# 02-ESP-WROOM-32.net
KiCad netlist of a schematic drawn in Altium Designer
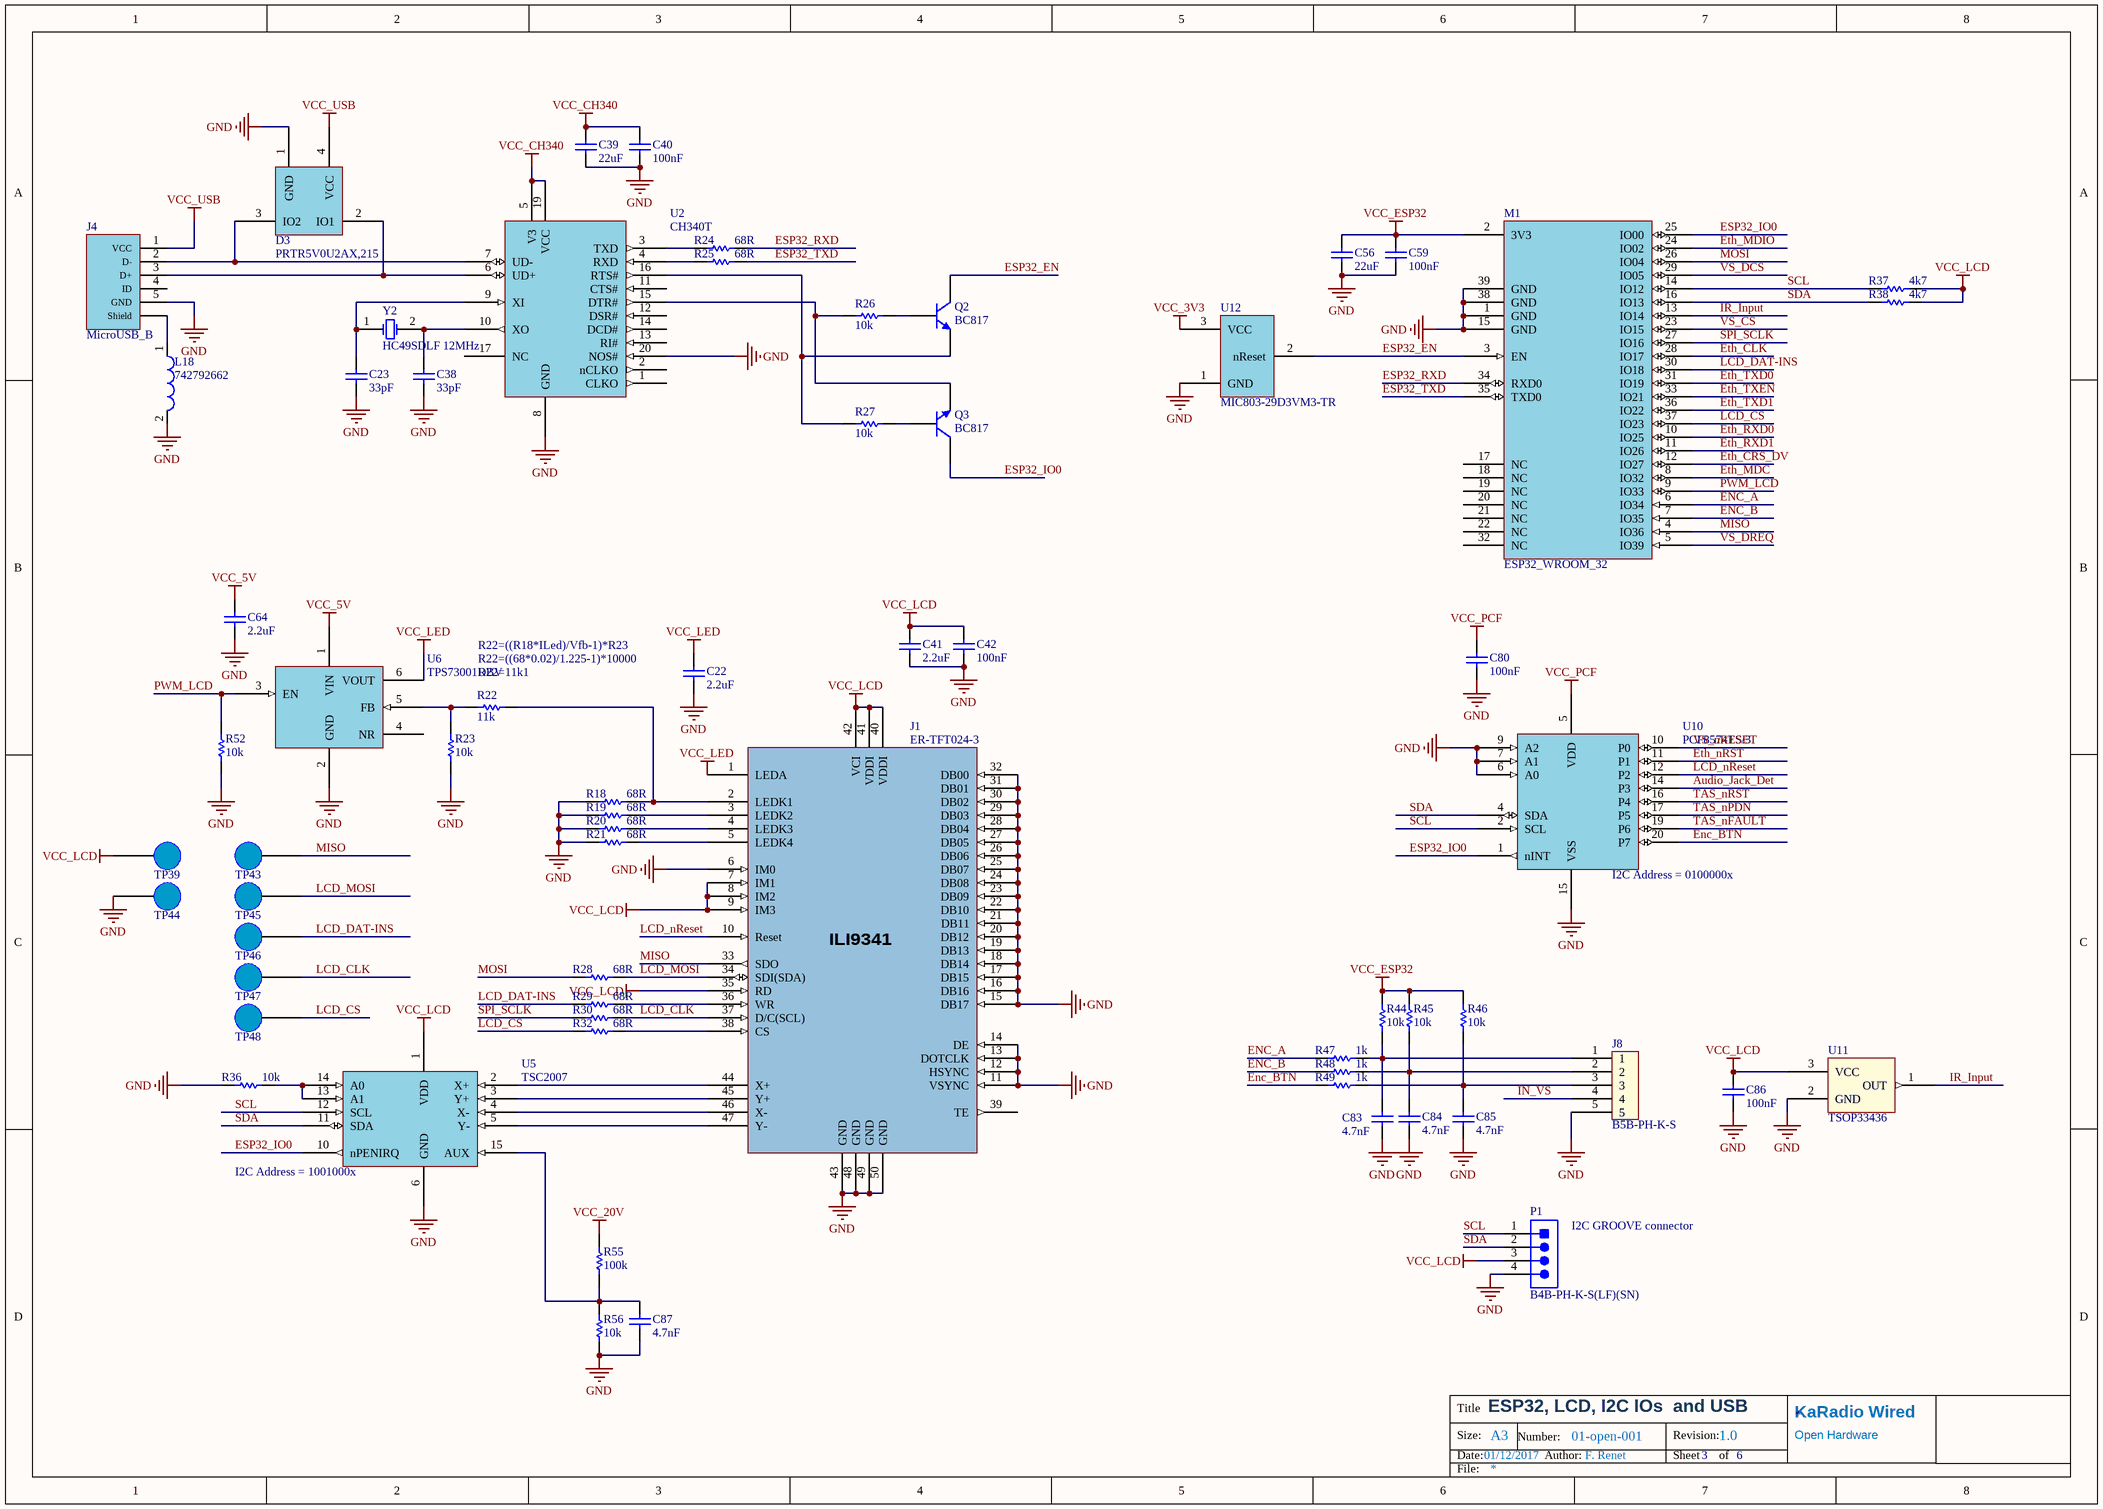
[diagram p0: 02-ESP-WROOM-32.SchDoc]

(export (version "E")
  (design (tool "Eeschema 10.0.6"))
  (components
    (comp (ref "C22")
      (value "2.2uF")
      (footprint "Aptustech:CAPC1608X06N")
      (description "2.2uF 10V 0603 X5R")
      (fields (field (name "VOLTAGE") "10V") (field (name "TOLERANCE") "10%"))
      (libsource (lib "Cap_0603") (part "2.2uF 10V 0603 X5R"))
    )
    (comp (ref "C23")
      (value "33pF")
      (footprint "Aptustech:CAPC1608X06N")
      (description "33pF 50V 0603 NP0")
      (fields (field (name "VOLTAGE") "50V") (field (name "TOLERANCE") "10%"))
      (libsource (lib "Cap_0603") (part "33pF 50V 0603 NP0"))
    )
    (comp (ref "C38")
      (value "33pF")
      (footprint "Aptustech:CAPC1608X06N")
      (description "33pF 50V 0603 NP0")
      (fields (field (name "VOLTAGE") "50V") (field (name "TOLERANCE") "10%"))
      (libsource (lib "Cap_0603") (part "33pF 50V 0603 NP0"))
    )
    (comp (ref "C39")
      (value "22uF")
      (footprint "Aptustech:CAPC1608X06N")
      (description "22uF 6.3V 0603 X5R")
      (fields (field (name "VOLTAGE") "6.3V") (field (name "TOLERANCE") "10%"))
      (libsource (lib "Cap_0603") (part "22uF 6.3V 0603 X5R"))
    )
    (comp (ref "C40")
      (value "100nF")
      (footprint "Aptustech:CAPC1608X06N")
      (description "100nF 25V 0603 X5R")
      (fields (field (name "VOLTAGE") "25V") (field (name "TOLERANCE") "10%"))
      (libsource (lib "Cap_0603") (part "100nF 25V 0603 X5R"))
    )
    (comp (ref "C41")
      (value "2.2uF")
      (footprint "Aptustech:CAPC1608X06N")
      (description "2.2uF 10V 0603 X5R")
      (fields (field (name "VOLTAGE") "10V") (field (name "TOLERANCE") "10%"))
      (libsource (lib "Cap_0603") (part "2.2uF 10V 0603 X5R"))
    )
    (comp (ref "C42")
      (value "100nF")
      (footprint "Aptustech:CAPC1608X06N")
      (description "100nF 25V 0603 X5R")
      (fields (field (name "VOLTAGE") "25V") (field (name "TOLERANCE") "10%"))
      (libsource (lib "Cap_0603") (part "100nF 25V 0603 X5R"))
    )
    (comp (ref "C56")
      (value "22uF")
      (footprint "Aptustech:CAPC1608X06N")
      (description "22uF 6.3V 0603 X5R")
      (fields (field (name "VOLTAGE") "6.3V") (field (name "TOLERANCE") "10%"))
      (libsource (lib "Cap_0603") (part "22uF 6.3V 0603 X5R"))
    )
    (comp (ref "C59")
      (value "100nF")
      (footprint "Aptustech:CAPC1608X06N")
      (description "100nF 25V 0603 X5R")
      (fields (field (name "VOLTAGE") "25V") (field (name "TOLERANCE") "10%"))
      (libsource (lib "Cap_0603") (part "100nF 25V 0603 X5R"))
    )
    (comp (ref "C64")
      (value "2.2uF")
      (footprint "Aptustech:CAPC1608X06N")
      (description "2.2uF 10V 0603 X5R")
      (fields (field (name "VOLTAGE") "10V") (field (name "TOLERANCE") "10%"))
      (libsource (lib "Cap_0603") (part "2.2uF 10V 0603 X5R"))
    )
    (comp (ref "C80")
      (value "100nF")
      (footprint "Aptustech:CAPC1608X06N")
      (description "100nF 25V 0603 X5R")
      (fields (field (name "VOLTAGE") "25V") (field (name "TOLERANCE") "10%"))
      (libsource (lib "Cap_0603") (part "100nF 25V 0603 X5R"))
    )
    (comp (ref "C83")
      (value "4.7nF")
      (footprint "CAPC1608X06N")
      (description "4.7nF 50V 0603 X7R")
      (fields (field (name "VOLTAGE") "50V") (field (name "TOLERANCE") "10%"))
      (libsource (lib "Cap_0603") (part "4.7nF 50V 0603 X7R"))
    )
    (comp (ref "C84")
      (value "4.7nF")
      (footprint "CAPC1608X06N")
      (description "4.7nF 50V 0603 X7R")
      (fields (field (name "VOLTAGE") "50V") (field (name "TOLERANCE") "10%"))
      (libsource (lib "Cap_0603") (part "4.7nF 50V 0603 X7R"))
    )
    (comp (ref "C85")
      (value "4.7nF")
      (footprint "CAPC1608X06N")
      (description "4.7nF 50V 0603 X7R")
      (fields (field (name "VOLTAGE") "50V") (field (name "TOLERANCE") "10%"))
      (libsource (lib "Cap_0603") (part "4.7nF 50V 0603 X7R"))
    )
    (comp (ref "C86")
      (value "100nF")
      (footprint "CAPC1608X06N")
      (description "100nF 25V 0603 X5R")
      (fields (field (name "VOLTAGE") "25V") (field (name "TOLERANCE") "10%"))
      (libsource (lib "Cap_0603") (part "100nF 25V 0603 X5R"))
    )
    (comp (ref "C87")
      (value "4.7nF")
      (footprint "Aptustech:CAPC1608X06N")
      (description "4.7nF 50V 0603 X7R")
      (fields (field (name "VOLTAGE") "50V") (field (name "TOLERANCE") "10%"))
      (libsource (lib "Cap_0603") (part "4.7nF 50V 0603 X7R"))
    )
    (comp (ref "D3")
      (value "PRTR5V0U2AX,215")
      (footprint "Aptustech:SOT190P230X120-4N")
      (description "Ultra low capacitance double rail-to-rail ESD protection diode")
      (fields (field (name "MANUFACTURER") "Nexperia"))
      (libsource (lib "Diodes") (part "PRTR5V0U2AX,215"))
    )
    (comp (ref "J1")
      (value "ER-TFT024-3")
      (footprint "Aptustech:62684-501100ALF")
      (description "Connector for 240x320 dots 2.4\" color tft lcd module")
      (fields (field (name "PARTNUMBER") "62684-501100ALF") (field (name "MANUFACTURER") "Amphenol FCI"))
      (libsource (lib "AptusTech") (part "ER-TFT024-3"))
    )
    (comp (ref "J4")
      (value "MicroUSB_B")
      (footprint "Aptustech:629105150521")
      (description "Micro USB 2.0 SMT Type B Horizontal")
      (fields (field (name "PARTNUMBER") "629105150521") (field (name "MANUFACTURER") "Wurth Elektronik"))
      (libsource (lib "Connectors") (part "MicroUSB_B"))
    )
    (comp (ref "J8")
      (value "B5B-PH-K-S")
      (footprint "PcbLib:JST-B5B-PH-K-S_V")
      (description "JST  B5B-PH 2mm Pitch 5pins TH")
      (fields (field (name "MANUFACTURER") "JST") (field (name "PARTNUMBER") "B5B-PH-K-S"))
      (libsource (lib "Connectors") (part "B5B-PH-K-S"))
    )
    (comp (ref "L18")
      (value "742792662")
      (footprint "CAPC0603(1608)")
      (description "SMD EMI Suppression Ferrite Bead WE-CBF, Z = 1000 Ohm")
      (fields (field (name "MANUFACTURER") "Wurth"))
      (libsource (lib "altium-import") (part "root_3_CMP-0220-00178-1_"))
    )
    (comp (ref "M1")
      (value "ESP32_WROOM_32")
      (footprint "Aptustech:ESP-WROOM-32")
      (fields (field (name "MANUFACTURER") "Espressif Systems"))
      (libsource (lib "Modules") (part "ESP32_WROOM_32"))
    )
    (comp (ref "P1")
      (value "B4B-PH-K-S(LF)(SN)")
      (footprint "Aptustech:JST-B4B-PH-K-S_V")
      (description "Male Header, Pitch 2 mm, 1 x 4 Position")
      (fields (field (name "MANUFACTURER") "JST"))
      (libsource (lib "altium-import") (part "root_0_CN-1P-M-R4_"))
    )
    (comp (ref "Q2")
      (value "BC817")
      (footprint "Aptustech:SOT95P230X110-3N")
      (description "BC817 NPN  45V SOT23")
      (fields (field (name "PARTNUMBER") "BC817-40,215") (field (name "MANUFACTURER") "Nexperia"))
      (libsource (lib "Transistor_Switch") (part "BC817_SOT23"))
    )
    (comp (ref "Q3")
      (value "BC817")
      (footprint "Aptustech:SOT95P230X110-3N")
      (description "BC817 NPN  45V SOT23")
      (fields (field (name "PARTNUMBER") "BC817-40,215") (field (name "MANUFACTURER") "Nexperia"))
      (libsource (lib "Transistor_Switch") (part "BC817_SOT23"))
    )
    (comp (ref "R18")
      (value "68R")
      (footprint "Aptustech:RESC1608X06N")
      (description "Resistor 68R 0603 1%")
      (fields (field (name "TOLERANCE") "1%") (field (name "Comment") "68R_0603"))
      (libsource (lib "Res_0603") (part "68R"))
    )
    (comp (ref "R19")
      (value "68R")
      (footprint "Aptustech:RESC1608X06N")
      (description "Resistor 68R 0603 1%")
      (fields (field (name "TOLERANCE") "1%") (field (name "Comment") "68R_0603"))
      (libsource (lib "Res_0603") (part "68R"))
    )
    (comp (ref "R20")
      (value "68R")
      (footprint "Aptustech:RESC1608X06N")
      (description "Resistor 68R 0603 1%")
      (fields (field (name "TOLERANCE") "1%") (field (name "Comment") "68R_0603"))
      (libsource (lib "Res_0603") (part "68R"))
    )
    (comp (ref "R21")
      (value "68R")
      (footprint "Aptustech:RESC1608X06N")
      (description "Resistor 68R 0603 1%")
      (fields (field (name "TOLERANCE") "1%") (field (name "Comment") "68R_0603"))
      (libsource (lib "Res_0603") (part "68R"))
    )
    (comp (ref "R22")
      (value "11k")
      (footprint "Aptustech:RESC1608X06N")
      (description "Resistor 11k 0603 1%")
      (fields (field (name "TOLERANCE") "1%") (field (name "Comment") "11k_0603"))
      (libsource (lib "Res_0603") (part "11k"))
    )
    (comp (ref "R23")
      (value "10k")
      (footprint "Aptustech:RESC1608X06N")
      (description "Resistor 10k 0603 1%")
      (fields (field (name "TOLERANCE") "1%") (field (name "Comment") "10k_0603"))
      (libsource (lib "Res_0603") (part "10k"))
    )
    (comp (ref "R24")
      (value "68R")
      (footprint "Aptustech:RESC1608X06N")
      (description "Resistor 68R 0603 1%")
      (fields (field (name "TOLERANCE") "1%") (field (name "Comment") "68R_0603"))
      (libsource (lib "Res_0603") (part "68R"))
    )
    (comp (ref "R25")
      (value "68R")
      (footprint "Aptustech:RESC1608X06N")
      (description "Resistor 68R 0603 1%")
      (fields (field (name "TOLERANCE") "1%") (field (name "Comment") "68R_0603"))
      (libsource (lib "Res_0603") (part "68R"))
    )
    (comp (ref "R26")
      (value "10k")
      (footprint "Aptustech:RESC1608X06N")
      (description "Resistor 10k 0603 1%")
      (fields (field (name "TOLERANCE") "1%") (field (name "Comment") "10k_0603"))
      (libsource (lib "Res_0603") (part "10k"))
    )
    (comp (ref "R27")
      (value "10k")
      (footprint "Aptustech:RESC1608X06N")
      (description "Resistor 10k 0603 1%")
      (fields (field (name "TOLERANCE") "1%") (field (name "Comment") "10k_0603"))
      (libsource (lib "Res_0603") (part "10k"))
    )
    (comp (ref "R28")
      (value "68R")
      (footprint "Aptustech:RESC1608X06N")
      (description "Resistor 68R 0603 1%")
      (fields (field (name "TOLERANCE") "1%") (field (name "Comment") "68R_0603"))
      (libsource (lib "Res_0603") (part "68R"))
    )
    (comp (ref "R29")
      (value "68R")
      (footprint "Aptustech:RESC1608X06N")
      (description "Resistor 68R 0603 1%")
      (fields (field (name "TOLERANCE") "1%") (field (name "Comment") "68R_0603"))
      (libsource (lib "Res_0603") (part "68R"))
    )
    (comp (ref "R30")
      (value "68R")
      (footprint "Aptustech:RESC1608X06N")
      (description "Resistor 68R 0603 1%")
      (fields (field (name "TOLERANCE") "1%") (field (name "Comment") "68R_0603"))
      (libsource (lib "Res_0603") (part "68R"))
    )
    (comp (ref "R32")
      (value "68R")
      (footprint "Aptustech:RESC1608X06N")
      (description "Resistor 68R 0603 1%")
      (fields (field (name "TOLERANCE") "1%") (field (name "Comment") "68R_0603"))
      (libsource (lib "Res_0603") (part "68R"))
    )
    (comp (ref "R36")
      (value "10k")
      (footprint "Aptustech:RESC1608X06N")
      (description "Resistor 10k 0603 1%")
      (fields (field (name "TOLERANCE") "1%") (field (name "Comment") "10k_0603"))
      (libsource (lib "Res_0603") (part "10k"))
    )
    (comp (ref "R37")
      (value "4k7")
      (footprint "Aptustech:RESC1608X06N")
      (description "Resistor 4k7 0603 1%")
      (fields (field (name "TOLERANCE") "1%") (field (name "Comment") "4k7_0603"))
      (libsource (lib "Res_0603") (part "4k7"))
    )
    (comp (ref "R38")
      (value "4k7")
      (footprint "Aptustech:RESC1608X06N")
      (description "Resistor 4k7 0603 1%")
      (fields (field (name "TOLERANCE") "1%") (field (name "Comment") "4k7_0603"))
      (libsource (lib "Res_0603") (part "4k7"))
    )
    (comp (ref "R44")
      (value "10k")
      (footprint "RESC1608X06N")
      (description "Resistor 10k 0603 1%")
      (fields (field (name "TOLERANCE") "1%") (field (name "Comment") "10k_0603"))
      (libsource (lib "Res_0603") (part "10k"))
    )
    (comp (ref "R45")
      (value "10k")
      (footprint "RESC1608X06N")
      (description "Resistor 10k 0603 1%")
      (fields (field (name "TOLERANCE") "1%") (field (name "Comment") "10k_0603"))
      (libsource (lib "Res_0603") (part "10k"))
    )
    (comp (ref "R46")
      (value "10k")
      (footprint "RESC1608X06N")
      (description "Resistor 10k 0603 1%")
      (fields (field (name "TOLERANCE") "1%") (field (name "Comment") "10k_0603"))
      (libsource (lib "Res_0603") (part "10k"))
    )
    (comp (ref "R47")
      (value "1k")
      (footprint "RESC1608X06N")
      (description "Resistor 1k 0603 1%")
      (fields (field (name "TOLERANCE") "1%") (field (name "Comment") "1k_0603"))
      (libsource (lib "Res_0603") (part "1k"))
    )
    (comp (ref "R48")
      (value "1k")
      (footprint "RESC1608X06N")
      (description "Resistor 1k 0603 1%")
      (fields (field (name "TOLERANCE") "1%") (field (name "Comment") "1k_0603"))
      (libsource (lib "Res_0603") (part "1k"))
    )
    (comp (ref "R49")
      (value "1k")
      (footprint "RESC1608X06N")
      (description "Resistor 1k 0603 1%")
      (fields (field (name "TOLERANCE") "1%") (field (name "Comment") "1k_0603"))
      (libsource (lib "Res_0603") (part "1k"))
    )
    (comp (ref "R52")
      (value "10k")
      (footprint "Aptustech:RESC1608X06N")
      (description "Resistor 10k 0603 1%")
      (fields (field (name "TOLERANCE") "1%") (field (name "Comment") "10k_0603"))
      (libsource (lib "Res_0603") (part "10k"))
    )
    (comp (ref "R55")
      (value "100k")
      (footprint "Aptustech:RESC1608X06N")
      (description "Resistor 100k 0603 1%")
      (fields (field (name "TOLERANCE") "1%") (field (name "Comment") "100k_0603"))
      (libsource (lib "Res_0603") (part "100k"))
    )
    (comp (ref "R56")
      (value "10k")
      (footprint "Aptustech:RESC1608X06N")
      (description "Resistor 10k 0603 1%")
      (fields (field (name "TOLERANCE") "1%") (field (name "Comment") "10k_0603"))
      (libsource (lib "Res_0603") (part "10k"))
    )
    (comp (ref "TP39")
      (value "TP_1mm")
      (footprint "Aptustech:TP_1mm")
      (description "Test point 1mm round SMD")
      (libsource (lib "Mech") (part "TP_1mm"))
    )
    (comp (ref "TP43")
      (value "TP_1mm")
      (footprint "Aptustech:TP_1mm")
      (description "Test point 1mm round SMD")
      (libsource (lib "Mech") (part "TP_1mm"))
    )
    (comp (ref "TP44")
      (value "TP_1mm")
      (footprint "Aptustech:TP_1mm")
      (description "Test point 1mm round SMD")
      (libsource (lib "Mech") (part "TP_1mm"))
    )
    (comp (ref "TP45")
      (value "TP_1mm")
      (footprint "Aptustech:TP_1mm")
      (description "Test point 1mm round SMD")
      (libsource (lib "Mech") (part "TP_1mm"))
    )
    (comp (ref "TP46")
      (value "TP_1mm")
      (footprint "Aptustech:TP_1mm")
      (description "Test point 1mm round SMD")
      (libsource (lib "Mech") (part "TP_1mm"))
    )
    (comp (ref "TP47")
      (value "TP_1mm")
      (footprint "Aptustech:TP_1mm")
      (description "Test point 1mm round SMD")
      (libsource (lib "Mech") (part "TP_1mm"))
    )
    (comp (ref "TP48")
      (value "TP_1mm")
      (footprint "Aptustech:TP_1mm")
      (description "Test point 1mm round SMD")
      (libsource (lib "Mech") (part "TP_1mm"))
    )
    (comp (ref "U2")
      (value "CH340T")
      (footprint "Aptustech:TSOP65P780X120-20N")
      (description "CH340T USB to Serial")
      (fields (field (name "MANUFACTURER") "WCH"))
      (libsource (lib "MISC_IC") (part "CH340T"))
    )
    (comp (ref "U5")
      (value "TSC2007")
      (footprint "Aptustech:TSOP65P640X120-16N")
      (description "TSSOP I2C Resistive Touch Controller")
      (fields (field (name "PARTNUMBER") "TSC2007IPWR") (field (name "MANUFACTURER") "TI"))
      (libsource (lib "MISC_IC") (part "TSC2007"))
    )
    (comp (ref "U6")
      (value "TPS73001DBV")
      (footprint "Aptustech:SOT95P245X110-6N")
      (description "TPS730 ADJ 200mA SOT23-6 LDO")
      (fields (field (name "MANUFACTURER") "TI"))
      (libsource (lib "LDO_DC-DC") (part "TPS73001DBV"))
    )
    (comp (ref "U10")
      (value "PCF8574TS/3")
      (footprint "Aptustech:TSOP65P640X120-20N")
      (description "PCF8574TS/3 SSOP20 I2C I/O Expander")
      (fields (field (name "MANUFACTURER") "NXP"))
      (libsource (lib "MISC_IC") (part "PCF8574TS/3"))
    )
    (comp (ref "U11")
      (value "TSOP33436")
      (footprint "PcbLib:TSOP332")
      (description "TSOP33436 IR 36kHz Receiver")
      (fields (field (name "MANUFACTURER") "Vishay"))
      (libsource (lib "KaRAD_EXT") (part "TSOP33436"))
    )
    (comp (ref "U12")
      (value "MIC803-29D3VM3-TR")
      (footprint "Aptustech:SOT95P230X110-3N")
      (description "Reset 2.93V open drain sot23 MIC803-29D3VM3-TR")
      (fields (field (name "MANUFACTURER") "Microchip"))
      (libsource (lib "MISC_IC") (part "MIC803-29D3VM3-TR"))
    )
    (comp (ref "Y2")
      (value "HC49SDLF 12MHz")
      (footprint "Aptustech:TXC 9C")
      (description "12.0000MHz Crystal HC49 SMT 20ppm")
      (fields (field (name "PARTNUMBER") "GC1200052") (field (name "MANUFACTURER") "Diodes"))
      (libsource (lib "Crystal_OSC") (part "HC49SDLF 12.000MHz"))
    )
  )
  (nets
    (net (code "1") (name "/Audio_Jack_Det") (class "Default")
      (node (ref "U10") (pin "14") (pinfunction "P3_14") (pintype "bidirectional"))
    )
    (net (code "2") (name "/ENC_A") (class "Default")
      (node (ref "M1") (pin "6") (pinfunction "IO34_6") (pintype "input"))
      (node (ref "R47") (pin "1") (pinfunction "1_1") (pintype "passive"))
    )
    (net (code "3") (name "/ENC_B") (class "Default")
      (node (ref "M1") (pin "7") (pinfunction "IO35_7") (pintype "input"))
      (node (ref "R48") (pin "1") (pinfunction "1_1") (pintype "passive"))
    )
    (net (code "4") (name "/ESP32_EN") (class "Default")
      (node (ref "M1") (pin "3") (pinfunction "EN_3") (pintype "input"))
      (node (ref "Q2") (pin "3") (pinfunction "C_3") (pintype "passive"))
      (node (ref "U12") (pin "2") (pinfunction "nReset_2") (pintype "open_collector"))
    )
    (net (code "5") (name "/ESP32_IO0") (class "Default")
      (node (ref "M1") (pin "25") (pinfunction "IO00_25") (pintype "bidirectional"))
      (node (ref "Q3") (pin "3") (pinfunction "C_3") (pintype "passive"))
      (node (ref "U10") (pin "1") (pinfunction "nINT_1") (pintype "output"))
      (node (ref "U5") (pin "10") (pinfunction "nPENIRQ_10") (pintype "output"))
    )
    (net (code "6") (name "/ESP32_RXD") (class "Default")
      (node (ref "M1") (pin "34") (pinfunction "RXD0_34") (pintype "bidirectional"))
      (node (ref "R24") (pin "2") (pinfunction "2_2") (pintype "passive"))
    )
    (net (code "7") (name "/ESP32_TXD") (class "Default")
      (node (ref "M1") (pin "35") (pinfunction "TXD0_35") (pintype "bidirectional"))
      (node (ref "R25") (pin "2") (pinfunction "2_2") (pintype "passive"))
    )
    (net (code "8") (name "/Enc_BTN") (class "Default")
      (node (ref "R49") (pin "1") (pinfunction "1_1") (pintype "passive"))
      (node (ref "U10") (pin "20") (pinfunction "P7_20") (pintype "bidirectional"))
    )
    (net (code "9") (name "/Eth_CLK") (class "Default")
      (node (ref "M1") (pin "28") (pinfunction "IO17_28") (pintype "bidirectional"))
    )
    (net (code "10") (name "/Eth_CRS_DV") (class "Default")
      (node (ref "M1") (pin "12") (pinfunction "IO27_12") (pintype "bidirectional"))
    )
    (net (code "11") (name "/Eth_MDC") (class "Default")
      (node (ref "M1") (pin "8") (pinfunction "IO32_8") (pintype "bidirectional"))
    )
    (net (code "12") (name "/Eth_MDIO") (class "Default")
      (node (ref "M1") (pin "24") (pinfunction "IO02_24") (pintype "bidirectional"))
    )
    (net (code "13") (name "/Eth_RXD0") (class "Default")
      (node (ref "M1") (pin "10") (pinfunction "IO25_10") (pintype "bidirectional"))
    )
    (net (code "14") (name "/Eth_RXD1") (class "Default")
      (node (ref "M1") (pin "11") (pinfunction "IO26_11") (pintype "bidirectional"))
    )
    (net (code "15") (name "/Eth_TXD0") (class "Default")
      (node (ref "M1") (pin "31") (pinfunction "IO19_31") (pintype "bidirectional"))
    )
    (net (code "16") (name "/Eth_TXD1") (class "Default")
      (node (ref "M1") (pin "36") (pinfunction "IO22_36") (pintype "bidirectional"))
    )
    (net (code "17") (name "/Eth_TXEN") (class "Default")
      (node (ref "M1") (pin "33") (pinfunction "IO21_33") (pintype "bidirectional"))
    )
    (net (code "18") (name "/Eth_nRST") (class "Default")
      (node (ref "U10") (pin "11") (pinfunction "P1_11") (pintype "bidirectional"))
    )
    (net (code "19") (name "/IN_VS") (class "Default")
      (node (ref "J8") (pin "4") (pinfunction "4_4") (pintype "power_in"))
    )
    (net (code "20") (name "/IR_Input") (class "Default")
      (node (ref "M1") (pin "13") (pinfunction "IO14_13") (pintype "bidirectional"))
      (node (ref "U11") (pin "1") (pinfunction "OUT_1") (pintype "output"))
    )
    (net (code "21") (name "/LCD_CLK") (class "Default")
      (node (ref "J1") (pin "37") (pinfunction "D/C(SCL)_37") (pintype "input"))
      (node (ref "R30") (pin "2") (pinfunction "2_2") (pintype "passive"))
      (node (ref "TP47") (pin "1") (pinfunction "1_1") (pintype "passive"))
    )
    (net (code "22") (name "/LCD_CS") (class "Default")
      (node (ref "M1") (pin "37") (pinfunction "IO23_37") (pintype "bidirectional"))
      (node (ref "R32") (pin "1") (pinfunction "1_1") (pintype "passive"))
      (node (ref "TP48") (pin "1") (pinfunction "1_1") (pintype "passive"))
    )
    (net (code "23") (name "/LCD_DAT-INS") (class "Default")
      (node (ref "M1") (pin "30") (pinfunction "IO18_30") (pintype "bidirectional"))
      (node (ref "R29") (pin "1") (pinfunction "1_1") (pintype "passive"))
      (node (ref "TP46") (pin "1") (pinfunction "1_1") (pintype "passive"))
    )
    (net (code "24") (name "/LCD_MOSI") (class "Default")
      (node (ref "J1") (pin "34") (pinfunction "SDI(SDA)_34") (pintype "bidirectional"))
      (node (ref "R28") (pin "2") (pinfunction "2_2") (pintype "passive"))
      (node (ref "TP45") (pin "1") (pinfunction "1_1") (pintype "passive"))
    )
    (net (code "25") (name "/LCD_nReset") (class "Default")
      (node (ref "J1") (pin "10") (pinfunction "Reset_10") (pintype "input"))
      (node (ref "U10") (pin "12") (pinfunction "P2_12") (pintype "bidirectional"))
    )
    (net (code "26") (name "/MISO") (class "Default")
      (node (ref "J1") (pin "33") (pinfunction "SDO_33") (pintype "output"))
      (node (ref "M1") (pin "4") (pinfunction "IO36_4") (pintype "input"))
      (node (ref "TP43") (pin "1") (pinfunction "1_1") (pintype "passive"))
    )
    (net (code "27") (name "/MOSI") (class "Default")
      (node (ref "M1") (pin "26") (pinfunction "IO04_26") (pintype "bidirectional"))
      (node (ref "R28") (pin "1") (pinfunction "1_1") (pintype "passive"))
    )
    (net (code "28") (name "/PWM_LCD") (class "Default")
      (node (ref "M1") (pin "9") (pinfunction "IO33_9") (pintype "bidirectional"))
      (node (ref "R52") (pin "2") (pinfunction "2_2") (pintype "passive"))
      (node (ref "U6") (pin "3") (pinfunction "EN_3") (pintype "input"))
    )
    (net (code "29") (name "/SCL") (class "Default")
      (node (ref "M1") (pin "14") (pinfunction "IO12_14") (pintype "bidirectional"))
      (node (ref "P1") (pin "1") (pinfunction "1_1") (pintype "passive"))
      (node (ref "R37") (pin "1") (pinfunction "1_1") (pintype "passive"))
      (node (ref "U10") (pin "2") (pinfunction "SCL_2") (pintype "input"))
      (node (ref "U5") (pin "12") (pinfunction "SCL_12") (pintype "input"))
    )
    (net (code "30") (name "/SDA") (class "Default")
      (node (ref "M1") (pin "16") (pinfunction "IO13_16") (pintype "bidirectional"))
      (node (ref "P1") (pin "2") (pinfunction "2_2") (pintype "passive"))
      (node (ref "R38") (pin "1") (pinfunction "1_1") (pintype "passive"))
      (node (ref "U10") (pin "4") (pinfunction "SDA_4") (pintype "bidirectional"))
      (node (ref "U5") (pin "11") (pinfunction "SDA_11") (pintype "bidirectional"))
    )
    (net (code "31") (name "/SPI_SCLK") (class "Default")
      (node (ref "M1") (pin "27") (pinfunction "IO16_27") (pintype "bidirectional"))
      (node (ref "R30") (pin "1") (pinfunction "1_1") (pintype "passive"))
    )
    (net (code "32") (name "/TAS_nFAULT") (class "Default")
      (node (ref "U10") (pin "19") (pinfunction "P6_19") (pintype "bidirectional"))
    )
    (net (code "33") (name "/TAS_nPDN") (class "Default")
      (node (ref "U10") (pin "17") (pinfunction "P5_17") (pintype "bidirectional"))
    )
    (net (code "34") (name "/TAS_nRST") (class "Default")
      (node (ref "U10") (pin "16") (pinfunction "P4_16") (pintype "bidirectional"))
    )
    (net (code "35") (name "/VS_CS") (class "Default")
      (node (ref "M1") (pin "23") (pinfunction "IO15_23") (pintype "bidirectional"))
    )
    (net (code "36") (name "/VS_DCS") (class "Default")
      (node (ref "M1") (pin "29") (pinfunction "IO05_29") (pintype "bidirectional"))
    )
    (net (code "37") (name "/VS_DREQ") (class "Default")
      (node (ref "M1") (pin "5") (pinfunction "IO39_5") (pintype "input"))
    )
    (net (code "38") (name "/VS_nRESET") (class "Default")
      (node (ref "U10") (pin "10") (pinfunction "P0_10") (pintype "bidirectional"))
    )
    (net (code "39") (name "GND") (class "Default")
      (node (ref "C22") (pin "1") (pinfunction "1_1") (pintype "passive"))
      (node (ref "C23") (pin "1") (pinfunction "1_1") (pintype "passive"))
      (node (ref "C38") (pin "1") (pinfunction "1_1") (pintype "passive"))
      (node (ref "C39") (pin "2") (pinfunction "2_2") (pintype "passive"))
      (node (ref "C40") (pin "2") (pinfunction "2_2") (pintype "passive"))
      (node (ref "C41") (pin "1") (pinfunction "1_1") (pintype "passive"))
      (node (ref "C42") (pin "2") (pinfunction "2_2") (pintype "passive"))
      (node (ref "C56") (pin "2") (pinfunction "2_2") (pintype "passive"))
      (node (ref "C59") (pin "2") (pinfunction "2_2") (pintype "passive"))
      (node (ref "C64") (pin "1") (pinfunction "1_1") (pintype "passive"))
      (node (ref "C80") (pin "2") (pinfunction "2_2") (pintype "passive"))
      (node (ref "C83") (pin "1") (pinfunction "1_1") (pintype "passive"))
      (node (ref "C84") (pin "1") (pinfunction "1_1") (pintype "passive"))
      (node (ref "C85") (pin "1") (pinfunction "1_1") (pintype "passive"))
      (node (ref "C86") (pin "2") (pinfunction "2_2") (pintype "passive"))
      (node (ref "C87") (pin "1") (pinfunction "1_1") (pintype "passive"))
      (node (ref "D3") (pin "1") (pinfunction "GND_1") (pintype "power_in"))
      (node (ref "J1") (pin "11") (pinfunction "VSYNC_11") (pintype "input"))
      (node (ref "J1") (pin "12") (pinfunction "HSYNC_12") (pintype "input"))
      (node (ref "J1") (pin "13") (pinfunction "DOTCLK_13") (pintype "input"))
      (node (ref "J1") (pin "14") (pinfunction "DE_14") (pintype "input"))
      (node (ref "J1") (pin "15") (pinfunction "DB17_15") (pintype "input"))
      (node (ref "J1") (pin "16") (pinfunction "DB16_16") (pintype "input"))
      (node (ref "J1") (pin "17") (pinfunction "DB15_17") (pintype "input"))
      (node (ref "J1") (pin "18") (pinfunction "DB14_18") (pintype "input"))
      (node (ref "J1") (pin "19") (pinfunction "DB13_19") (pintype "input"))
      (node (ref "J1") (pin "20") (pinfunction "DB12_20") (pintype "input"))
      (node (ref "J1") (pin "21") (pinfunction "DB11_21") (pintype "input"))
      (node (ref "J1") (pin "22") (pinfunction "DB10_22") (pintype "input"))
      (node (ref "J1") (pin "23") (pinfunction "DB09_23") (pintype "input"))
      (node (ref "J1") (pin "24") (pinfunction "DB08_24") (pintype "input"))
      (node (ref "J1") (pin "25") (pinfunction "DB07_25") (pintype "input"))
      (node (ref "J1") (pin "26") (pinfunction "DB06_26") (pintype "input"))
      (node (ref "J1") (pin "27") (pinfunction "DB05_27") (pintype "input"))
      (node (ref "J1") (pin "28") (pinfunction "DB04_28") (pintype "input"))
      (node (ref "J1") (pin "29") (pinfunction "DB03_29") (pintype "input"))
      (node (ref "J1") (pin "30") (pinfunction "DB02_30") (pintype "input"))
      (node (ref "J1") (pin "31") (pinfunction "DB01_31") (pintype "input"))
      (node (ref "J1") (pin "32") (pinfunction "DB00_32") (pintype "input"))
      (node (ref "J1") (pin "43") (pinfunction "GND_43") (pintype "power_in"))
      (node (ref "J1") (pin "48") (pinfunction "GND_48") (pintype "power_in"))
      (node (ref "J1") (pin "49") (pinfunction "GND_49") (pintype "power_in"))
      (node (ref "J1") (pin "50") (pinfunction "GND_50") (pintype "power_in"))
      (node (ref "J1") (pin "6") (pinfunction "IM0_6") (pintype "input"))
      (node (ref "J4") (pin "5") (pinfunction "GND_5") (pintype "passive"))
      (node (ref "J8") (pin "5") (pinfunction "5_5") (pintype "power_in"))
      (node (ref "L18") (pin "2") (pinfunction "2_2") (pintype "passive"))
      (node (ref "M1") (pin "1") (pinfunction "GND_1") (pintype "power_in"))
      (node (ref "M1") (pin "15") (pinfunction "GND_15") (pintype "power_in"))
      (node (ref "M1") (pin "38") (pinfunction "GND_38") (pintype "power_in"))
      (node (ref "M1") (pin "39") (pinfunction "GND_39") (pintype "power_in"))
      (node (ref "P1") (pin "4") (pinfunction "4_4") (pintype "passive"))
      (node (ref "R18") (pin "1") (pinfunction "1_1") (pintype "passive"))
      (node (ref "R19") (pin "1") (pinfunction "1_1") (pintype "passive"))
      (node (ref "R20") (pin "1") (pinfunction "1_1") (pintype "passive"))
      (node (ref "R21") (pin "1") (pinfunction "1_1") (pintype "passive"))
      (node (ref "R23") (pin "1") (pinfunction "1_1") (pintype "passive"))
      (node (ref "R36") (pin "2") (pinfunction "2_2") (pintype "passive"))
      (node (ref "R52") (pin "1") (pinfunction "1_1") (pintype "passive"))
      (node (ref "R56") (pin "1") (pinfunction "1_1") (pintype "passive"))
      (node (ref "TP44") (pin "1") (pinfunction "1_1") (pintype "passive"))
      (node (ref "U10") (pin "15") (pinfunction "VSS_15") (pintype "power_in"))
      (node (ref "U10") (pin "6") (pinfunction "A0_6") (pintype "input"))
      (node (ref "U10") (pin "7") (pinfunction "A1_7") (pintype "input"))
      (node (ref "U10") (pin "9") (pinfunction "A2_9") (pintype "input"))
      (node (ref "U11") (pin "2") (pinfunction "GND_2") (pintype "power_in"))
      (node (ref "U12") (pin "1") (pinfunction "GND_1") (pintype "power_in"))
      (node (ref "U2") (pin "20") (pinfunction "NOS#_20") (pintype "input"))
      (node (ref "U2") (pin "8") (pinfunction "GND_8") (pintype "power_in"))
      (node (ref "U5") (pin "6") (pinfunction "GND_6") (pintype "power_in"))
      (node (ref "U6") (pin "2") (pinfunction "GND_2") (pintype "power_in"))
    )
    (net (code "40") (name "Net-(C83-Pad2)") (class "Default")
      (node (ref "C83") (pin "2") (pinfunction "2_2") (pintype "passive"))
      (node (ref "J8") (pin "1") (pinfunction "1_1") (pintype "passive"))
      (node (ref "R44") (pin "1") (pinfunction "1_1") (pintype "passive"))
      (node (ref "R47") (pin "2") (pinfunction "2_2") (pintype "passive"))
    )
    (net (code "41") (name "Net-(C84-Pad2)") (class "Default")
      (node (ref "C84") (pin "2") (pinfunction "2_2") (pintype "passive"))
      (node (ref "J8") (pin "2") (pinfunction "2_2") (pintype "passive"))
      (node (ref "R45") (pin "1") (pinfunction "1_1") (pintype "passive"))
      (node (ref "R48") (pin "2") (pinfunction "2_2") (pintype "passive"))
    )
    (net (code "42") (name "Net-(C85-Pad2)") (class "Default")
      (node (ref "C85") (pin "2") (pinfunction "2_2") (pintype "passive"))
      (node (ref "J8") (pin "3") (pinfunction "3_3") (pintype "power_in"))
      (node (ref "R46") (pin "1") (pinfunction "1_1") (pintype "passive"))
      (node (ref "R49") (pin "2") (pinfunction "2_2") (pintype "passive"))
    )
    (net (code "43") (name "Net-(D3-IO1)") (class "Default")
      (node (ref "D3") (pin "2") (pinfunction "IO1_2") (pintype "passive"))
      (node (ref "J4") (pin "3") (pinfunction "D+_3") (pintype "passive"))
      (node (ref "U2") (pin "6") (pinfunction "UD+_6") (pintype "bidirectional"))
    )
    (net (code "44") (name "Net-(D3-IO2)") (class "Default")
      (node (ref "D3") (pin "3") (pinfunction "IO2_3") (pintype "passive"))
      (node (ref "J4") (pin "2") (pinfunction "D-_2") (pintype "passive"))
      (node (ref "U2") (pin "7") (pinfunction "UD-_7") (pintype "bidirectional"))
    )
    (net (code "45") (name "Net-(J1-CS)") (class "Default")
      (node (ref "J1") (pin "38") (pinfunction "CS_38") (pintype "input"))
      (node (ref "R32") (pin "2") (pinfunction "2_2") (pintype "passive"))
    )
    (net (code "46") (name "Net-(J1-LEDK1)") (class "Default")
      (node (ref "J1") (pin "2") (pinfunction "LEDK1_2") (pintype "passive"))
      (node (ref "R18") (pin "2") (pinfunction "2_2") (pintype "passive"))
      (node (ref "R22") (pin "2") (pinfunction "2_2") (pintype "passive"))
    )
    (net (code "47") (name "Net-(J1-LEDK2)") (class "Default")
      (node (ref "J1") (pin "3") (pinfunction "LEDK2_3") (pintype "passive"))
      (node (ref "R19") (pin "2") (pinfunction "2_2") (pintype "passive"))
    )
    (net (code "48") (name "Net-(J1-LEDK3)") (class "Default")
      (node (ref "J1") (pin "4") (pinfunction "LEDK3_4") (pintype "passive"))
      (node (ref "R20") (pin "2") (pinfunction "2_2") (pintype "passive"))
    )
    (net (code "49") (name "Net-(J1-LEDK4)") (class "Default")
      (node (ref "J1") (pin "5") (pinfunction "LEDK4_5") (pintype "passive"))
      (node (ref "R21") (pin "2") (pinfunction "2_2") (pintype "passive"))
    )
    (net (code "50") (name "Net-(J1-WR)") (class "Default")
      (node (ref "J1") (pin "36") (pinfunction "WR_36") (pintype "input"))
      (node (ref "R29") (pin "2") (pinfunction "2_2") (pintype "passive"))
    )
    (net (code "51") (name "Net-(J1-X+)") (class "Default")
      (node (ref "J1") (pin "44") (pinfunction "X+_44") (pintype "passive"))
      (node (ref "U5") (pin "2") (pinfunction "X+_2") (pintype "input"))
    )
    (net (code "52") (name "Net-(J1-X-)") (class "Default")
      (node (ref "J1") (pin "46") (pinfunction "X-_46") (pintype "passive"))
      (node (ref "U5") (pin "4") (pinfunction "X-_4") (pintype "input"))
    )
    (net (code "53") (name "Net-(J1-Y+)") (class "Default")
      (node (ref "J1") (pin "45") (pinfunction "Y+_45") (pintype "passive"))
      (node (ref "U5") (pin "3") (pinfunction "Y+_3") (pintype "input"))
    )
    (net (code "54") (name "Net-(J1-Y-)") (class "Default")
      (node (ref "J1") (pin "47") (pinfunction "Y-_47") (pintype "passive"))
      (node (ref "U5") (pin "5") (pinfunction "Y-_5") (pintype "input"))
    )
    (net (code "55") (name "Net-(J4-Shield)") (class "Default")
      (node (ref "J4") (pin "Shell") (pinfunction "Shield_Shell") (pintype "passive"))
      (node (ref "L18") (pin "1") (pinfunction "1_1") (pintype "passive"))
    )
    (net (code "56") (name "Net-(Q2-B)") (class "Default")
      (node (ref "Q2") (pin "1") (pinfunction "B_1") (pintype "passive"))
      (node (ref "R26") (pin "1") (pinfunction "1_1") (pintype "passive"))
    )
    (net (code "57") (name "Net-(Q2-E)") (class "Default")
      (node (ref "Q2") (pin "2") (pinfunction "E_2") (pintype "passive"))
      (node (ref "R27") (pin "2") (pinfunction "2_2") (pintype "passive"))
      (node (ref "U2") (pin "16") (pinfunction "RTS#_16") (pintype "output"))
    )
    (net (code "58") (name "Net-(Q3-B)") (class "Default")
      (node (ref "Q3") (pin "1") (pinfunction "B_1") (pintype "passive"))
      (node (ref "R27") (pin "1") (pinfunction "1_1") (pintype "passive"))
    )
    (net (code "59") (name "Net-(Q3-E)") (class "Default")
      (node (ref "Q3") (pin "2") (pinfunction "E_2") (pintype "passive"))
      (node (ref "R26") (pin "2") (pinfunction "2_2") (pintype "passive"))
      (node (ref "U2") (pin "15") (pinfunction "DTR#_15") (pintype "output"))
    )
    (net (code "60") (name "Net-(U2-RXD)") (class "Default")
      (node (ref "R25") (pin "1") (pinfunction "1_1") (pintype "passive"))
      (node (ref "U2") (pin "4") (pinfunction "RXD_4") (pintype "input"))
    )
    (net (code "61") (name "Net-(U2-TXD)") (class "Default")
      (node (ref "R24") (pin "1") (pinfunction "1_1") (pintype "passive"))
      (node (ref "U2") (pin "3") (pinfunction "TXD_3") (pintype "output"))
    )
    (net (code "62") (name "Net-(U2-XI)") (class "Default")
      (node (ref "C23") (pin "2") (pinfunction "2_2") (pintype "passive"))
      (node (ref "U2") (pin "9") (pinfunction "XI_9") (pintype "input"))
      (node (ref "Y2") (pin "1") (pinfunction "OSC1_1") (pintype "passive"))
    )
    (net (code "63") (name "Net-(U2-XO)") (class "Default")
      (node (ref "C38") (pin "2") (pinfunction "2_2") (pintype "passive"))
      (node (ref "U2") (pin "10") (pinfunction "XO_10") (pintype "output"))
      (node (ref "Y2") (pin "2") (pinfunction "OSC2_2") (pintype "passive"))
    )
    (net (code "64") (name "Net-(U5-A0)") (class "Default")
      (node (ref "R36") (pin "1") (pinfunction "1_1") (pintype "passive"))
      (node (ref "U5") (pin "13") (pinfunction "A1_13") (pintype "input"))
      (node (ref "U5") (pin "14") (pinfunction "A0_14") (pintype "input"))
    )
    (net (code "65") (name "Net-(U5-AUX)") (class "Default")
      (node (ref "C87") (pin "2") (pinfunction "2_2") (pintype "passive"))
      (node (ref "R55") (pin "1") (pinfunction "1_1") (pintype "passive"))
      (node (ref "R56") (pin "2") (pinfunction "2_2") (pintype "passive"))
      (node (ref "U5") (pin "15") (pinfunction "AUX_15") (pintype "input"))
    )
    (net (code "66") (name "Net-(U6-FB)") (class "Default")
      (node (ref "R22") (pin "1") (pinfunction "1_1") (pintype "passive"))
      (node (ref "R23") (pin "2") (pinfunction "2_2") (pintype "passive"))
      (node (ref "U6") (pin "5") (pinfunction "FB_5") (pintype "input"))
    )
    (net (code "67") (name "VCC_3V3") (class "Default")
      (node (ref "U12") (pin "3") (pinfunction "VCC_3") (pintype "power_in"))
    )
    (net (code "68") (name "VCC_5V") (class "Default")
      (node (ref "C64") (pin "2") (pinfunction "2_2") (pintype "passive"))
      (node (ref "U6") (pin "1") (pinfunction "VIN_1") (pintype "power_in"))
    )
    (net (code "69") (name "VCC_20V") (class "Default")
      (node (ref "R55") (pin "2") (pinfunction "2_2") (pintype "passive"))
    )
    (net (code "70") (name "VCC_CH340") (class "Default")
      (node (ref "C39") (pin "1") (pinfunction "1_1") (pintype "passive"))
      (node (ref "C40") (pin "1") (pinfunction "1_1") (pintype "passive"))
      (node (ref "U2") (pin "19") (pinfunction "VCC_19") (pintype "power_in"))
      (node (ref "U2") (pin "5") (pinfunction "V3_5") (pintype "power_in"))
    )
    (net (code "71") (name "VCC_ESP32") (class "Default")
      (node (ref "C56") (pin "1") (pinfunction "1_1") (pintype "passive"))
      (node (ref "C59") (pin "1") (pinfunction "1_1") (pintype "passive"))
      (node (ref "M1") (pin "2") (pinfunction "3V3_2") (pintype "power_in"))
      (node (ref "R44") (pin "2") (pinfunction "2_2") (pintype "passive"))
      (node (ref "R45") (pin "2") (pinfunction "2_2") (pintype "passive"))
      (node (ref "R46") (pin "2") (pinfunction "2_2") (pintype "passive"))
    )
    (net (code "72") (name "VCC_LCD") (class "Default")
      (node (ref "C41") (pin "2") (pinfunction "2_2") (pintype "passive"))
      (node (ref "C42") (pin "1") (pinfunction "1_1") (pintype "passive"))
      (node (ref "C86") (pin "1") (pinfunction "1_1") (pintype "passive"))
      (node (ref "J1") (pin "35") (pinfunction "RD_35") (pintype "input"))
      (node (ref "J1") (pin "40") (pinfunction "VDDI_40") (pintype "power_in"))
      (node (ref "J1") (pin "41") (pinfunction "VDDI_41") (pintype "power_in"))
      (node (ref "J1") (pin "42") (pinfunction "VCI_42") (pintype "power_in"))
      (node (ref "J1") (pin "7") (pinfunction "IM1_7") (pintype "input"))
      (node (ref "J1") (pin "8") (pinfunction "IM2_8") (pintype "input"))
      (node (ref "J1") (pin "9") (pinfunction "IM3_9") (pintype "input"))
      (node (ref "P1") (pin "3") (pinfunction "3_3") (pintype "passive"))
      (node (ref "R37") (pin "2") (pinfunction "2_2") (pintype "passive"))
      (node (ref "R38") (pin "2") (pinfunction "2_2") (pintype "passive"))
      (node (ref "TP39") (pin "1") (pinfunction "1_1") (pintype "passive"))
      (node (ref "U11") (pin "3") (pinfunction "VCC_3") (pintype "power_in"))
      (node (ref "U5") (pin "1") (pinfunction "VDD_1") (pintype "power_in"))
    )
    (net (code "73") (name "VCC_LED") (class "Default")
      (node (ref "C22") (pin "2") (pinfunction "2_2") (pintype "passive"))
      (node (ref "J1") (pin "1") (pinfunction "LEDA_1") (pintype "passive"))
      (node (ref "U6") (pin "6") (pinfunction "VOUT_6") (pintype "power_in"))
    )
    (net (code "74") (name "VCC_PCF") (class "Default")
      (node (ref "C80") (pin "1") (pinfunction "1_1") (pintype "passive"))
      (node (ref "U10") (pin "5") (pinfunction "VDD_5") (pintype "power_in"))
    )
    (net (code "75") (name "VCC_USB") (class "Default")
      (node (ref "D3") (pin "4") (pinfunction "VCC_4") (pintype "power_in"))
      (node (ref "J4") (pin "1") (pinfunction "VCC_1") (pintype "passive"))
    )
    (net (code "76") (name "unconnected-(J1-TE-Pad39)") (class "Default")
      (node (ref "J1") (pin "39") (pinfunction "TE_39") (pintype "output"))
    )
    (net (code "77") (name "unconnected-(J4-ID-Pad4)") (class "Default")
      (node (ref "J4") (pin "4") (pinfunction "ID_4") (pintype "passive"))
    )
    (net (code "78") (name "unconnected-(M1-NC-Pad17)") (class "Default")
      (node (ref "M1") (pin "17") (pinfunction "NC_17") (pintype "passive"))
    )
    (net (code "79") (name "unconnected-(M1-NC-Pad18)") (class "Default")
      (node (ref "M1") (pin "18") (pinfunction "NC_18") (pintype "passive"))
    )
    (net (code "80") (name "unconnected-(M1-NC-Pad19)") (class "Default")
      (node (ref "M1") (pin "19") (pinfunction "NC_19") (pintype "passive"))
    )
    (net (code "81") (name "unconnected-(M1-NC-Pad20)") (class "Default")
      (node (ref "M1") (pin "20") (pinfunction "NC_20") (pintype "passive"))
    )
    (net (code "82") (name "unconnected-(M1-NC-Pad21)") (class "Default")
      (node (ref "M1") (pin "21") (pinfunction "NC_21") (pintype "passive"))
    )
    (net (code "83") (name "unconnected-(M1-NC-Pad22)") (class "Default")
      (node (ref "M1") (pin "22") (pinfunction "NC_22") (pintype "passive"))
    )
    (net (code "84") (name "unconnected-(M1-NC-Pad32)") (class "Default")
      (node (ref "M1") (pin "32") (pinfunction "NC_32") (pintype "passive"))
    )
    (net (code "85") (name "unconnected-(U2-CLKO-Pad1)") (class "Default")
      (node (ref "U2") (pin "1") (pinfunction "CLKO_1") (pintype "output"))
    )
    (net (code "86") (name "unconnected-(U2-CTS#-Pad11)") (class "Default")
      (node (ref "U2") (pin "11") (pinfunction "CTS#_11") (pintype "input"))
    )
    (net (code "87") (name "unconnected-(U2-DCD#-Pad14)") (class "Default")
      (node (ref "U2") (pin "14") (pinfunction "DCD#_14") (pintype "output"))
    )
    (net (code "88") (name "unconnected-(U2-DSR#-Pad12)") (class "Default")
      (node (ref "U2") (pin "12") (pinfunction "DSR#_12") (pintype "input"))
    )
    (net (code "89") (name "unconnected-(U2-NC-Pad17)") (class "Default")
      (node (ref "U2") (pin "17") (pinfunction "NC_17") (pintype "passive"))
    )
    (net (code "90") (name "unconnected-(U2-RI#-Pad13)") (class "Default")
      (node (ref "U2") (pin "13") (pinfunction "RI#_13") (pintype "input"))
    )
    (net (code "91") (name "unconnected-(U2-nCLKO-Pad2)") (class "Default")
      (node (ref "U2") (pin "2") (pinfunction "nCLKO_2") (pintype "output"))
    )
    (net (code "92") (name "unconnected-(U6-NR-Pad4)") (class "Default")
      (node (ref "U6") (pin "4") (pinfunction "NR_4") (pintype "passive"))
    )
  )
)
